# LKS_074DO_0319.net
KiCad netlist of a schematic drawn in Altium Designer
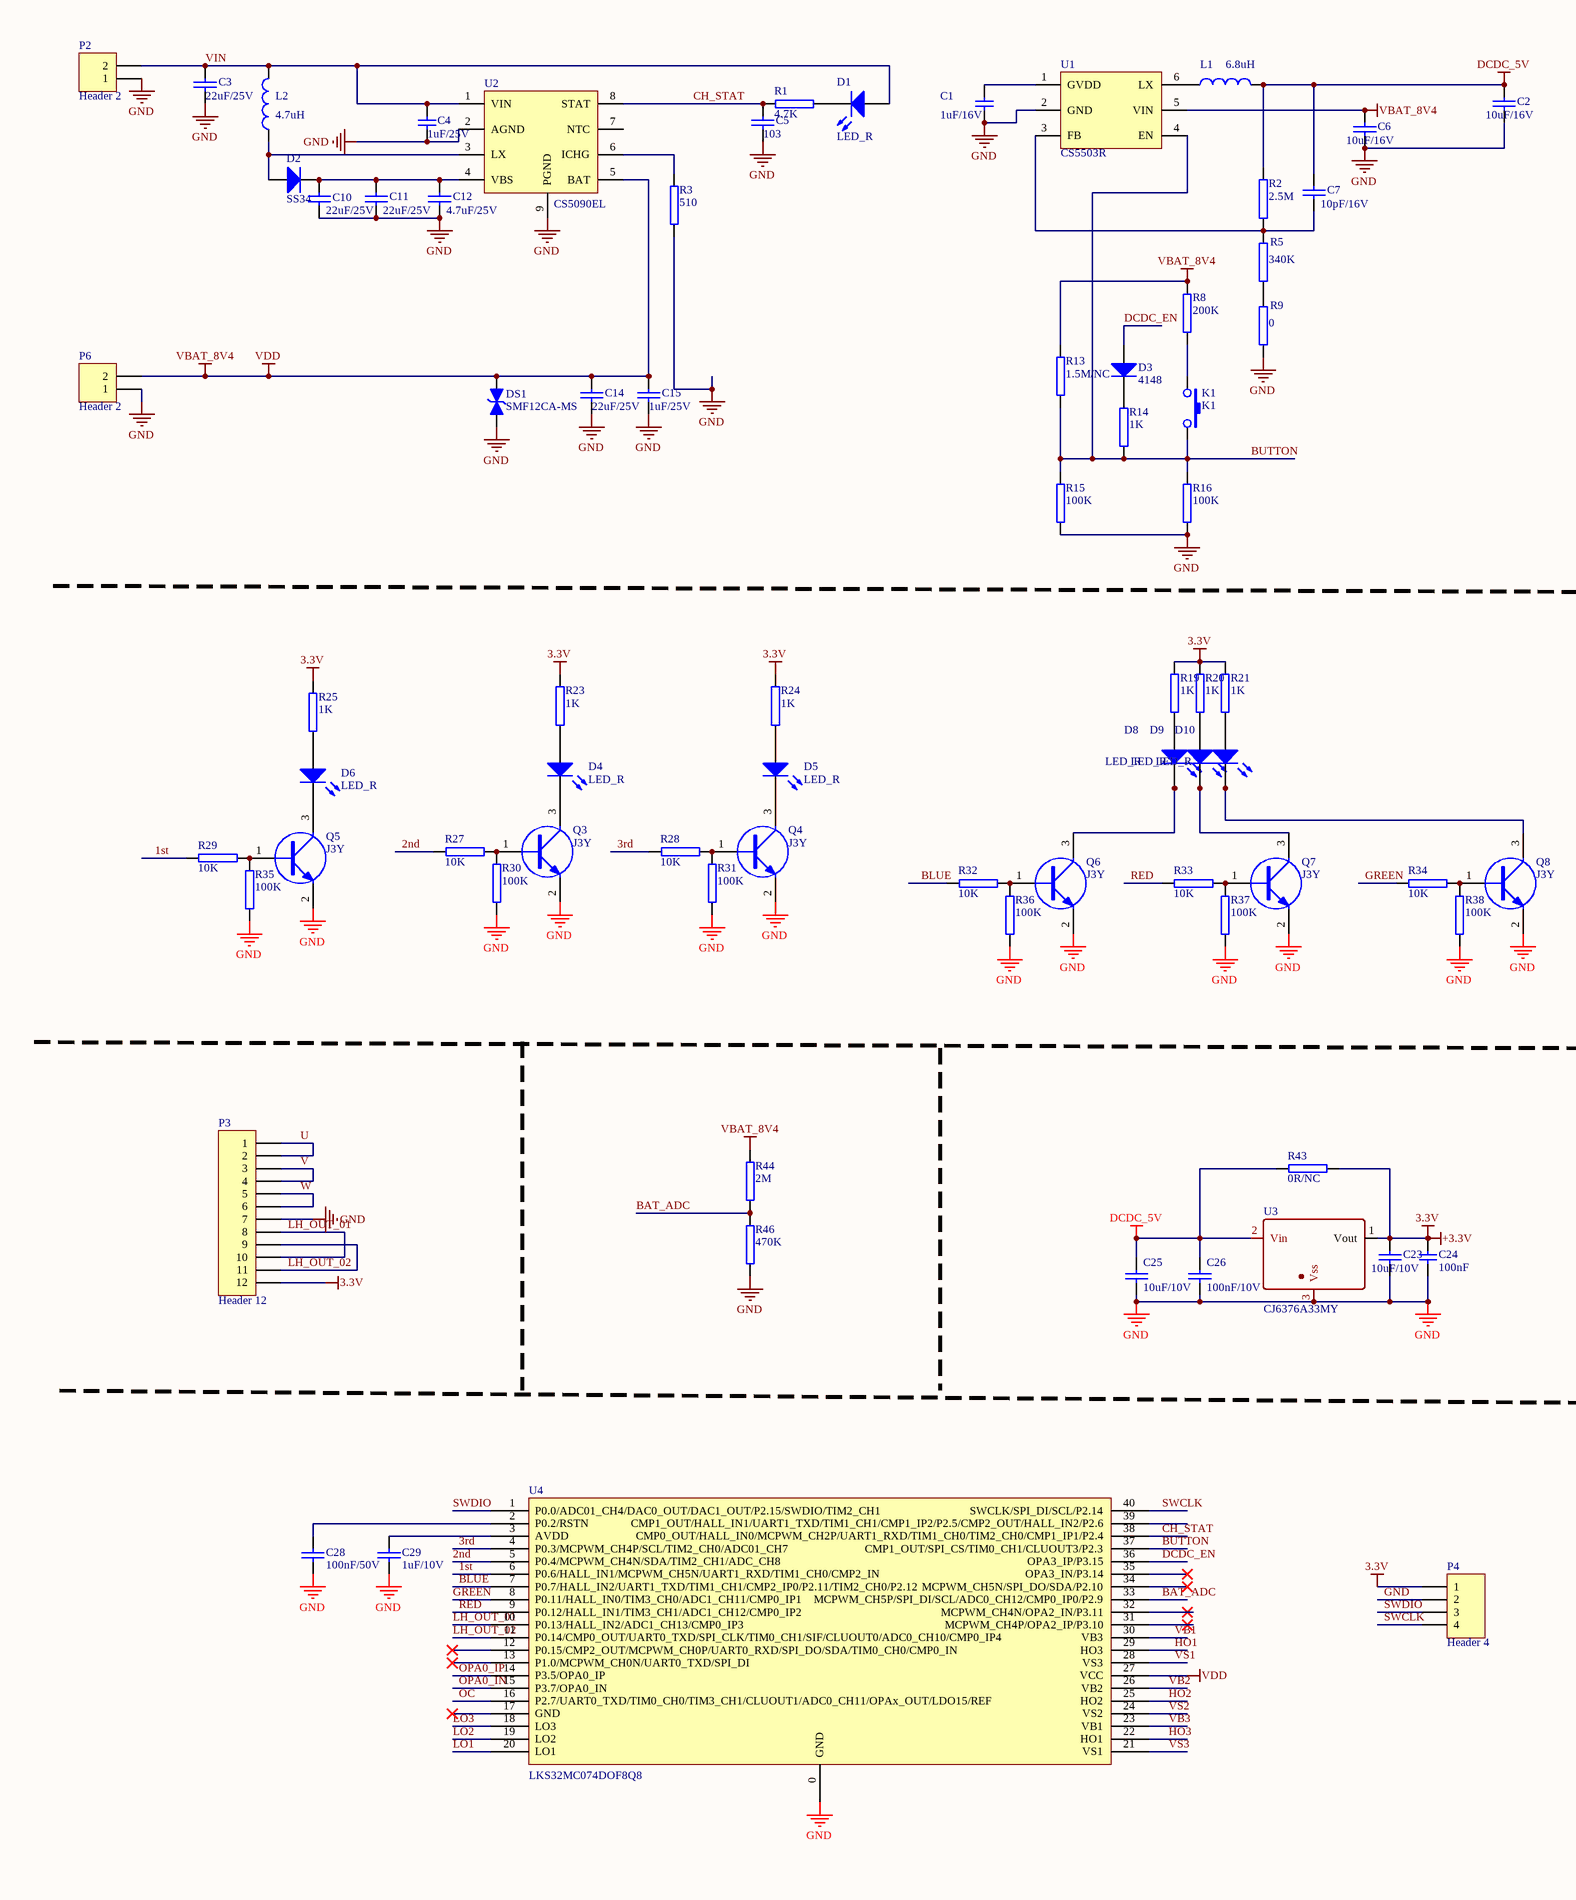
[diagram p0: LKS_074DO_0319.SchDoc, left]
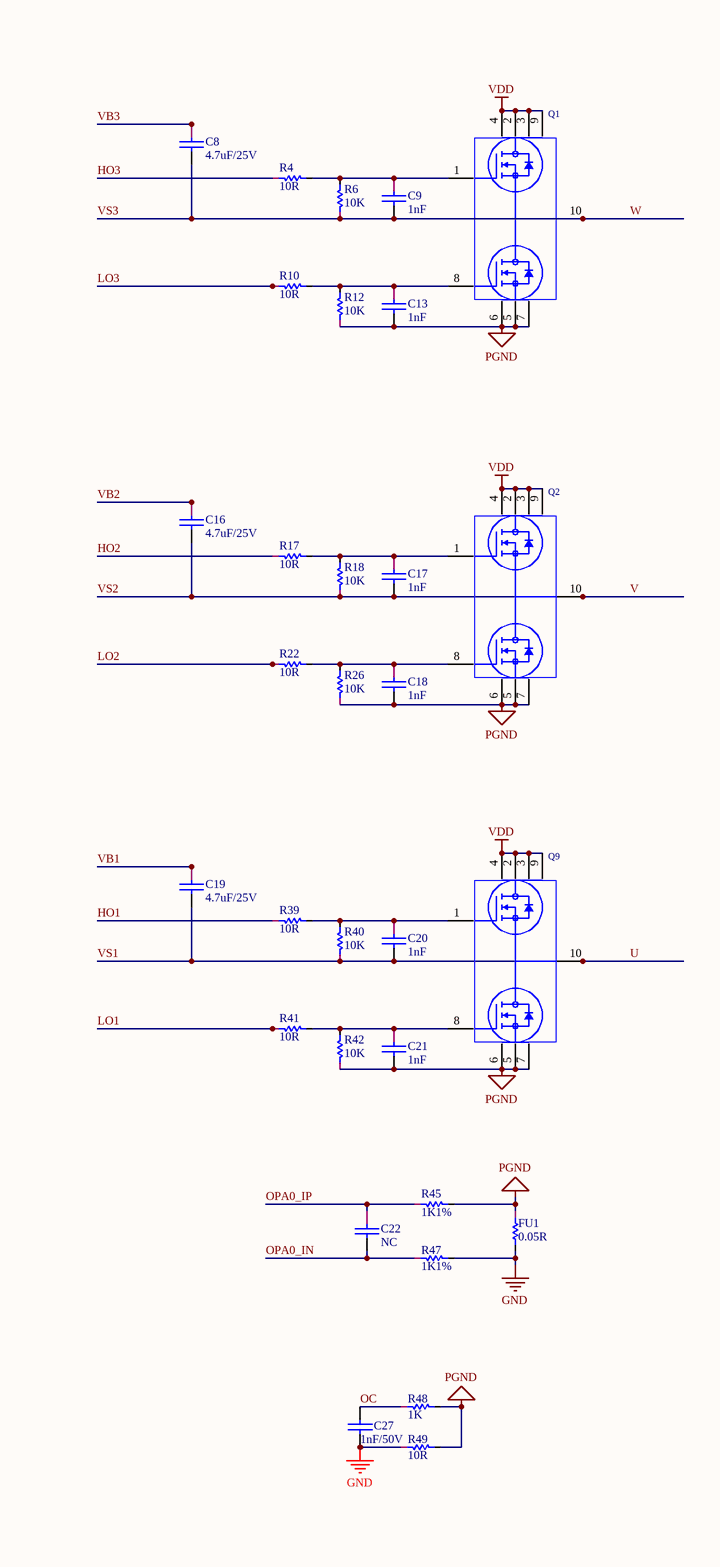
[diagram p1: LKS_074DO_0319.SchDoc, right]

(export (version "E")
  (design (tool "Eeschema 10.0.6"))
  (components
    (comp (ref "C1") (value "1uF/16V") (footprint "C 0402_M") (libsource (lib "") (part "CAP_2")))
    (comp (ref "C2")
      (value "10uF/16V")
      (footprint "C 0603_M")
      (description "Capacitor")
      (libsource (lib "") (part "CAP_1"))
    )
    (comp (ref "C3")
      (value "22uF/25V")
      (footprint "C 0603_M")
      (description "Capacitor")
      (libsource (lib "") (part "CAP_1"))
    )
    (comp (ref "C4") (value "1uF/25V") (footprint "C 0402_M") (libsource (lib "") (part "CAP_2")))
    (comp (ref "C5")
      (value "103")
      (footprint "R 0402_M")
      (description "Capacitor")
      (libsource (lib "") (part "CAP_1"))
    )
    (comp (ref "C6")
      (value "10uF/16V")
      (footprint "C 0603_M")
      (description "Capacitor")
      (libsource (lib "") (part "CAP_1"))
    )
    (comp (ref "C7")
      (value "10pF/16V")
      (footprint "C 0402_M")
      (description "Capacitor")
      (libsource (lib "") (part "CAP_1"))
    )
    (comp (ref "C8")
      (value "4.7uF/25V")
      (footprint "C 0402_M")
      (description "Capacitor")
      (libsource (lib "*") (part "CAP"))
    )
    (comp (ref "C9")
      (value "1nF")
      (footprint "C 0402_M")
      (description "Capacitor")
      (libsource (lib "*") (part "CAP"))
    )
    (comp (ref "C10")
      (value "22uF/25V")
      (footprint "C 0603_M")
      (description "Capacitor")
      (libsource (lib "") (part "CAP_1"))
    )
    (comp (ref "C11")
      (value "22uF/25V")
      (footprint "C 0603_M")
      (description "Capacitor")
      (libsource (lib "") (part "CAP_1"))
    )
    (comp (ref "C12")
      (value "4.7uF/25V")
      (footprint "C 0402_M")
      (description "Capacitor")
      (libsource (lib "") (part "CAP_1"))
    )
    (comp (ref "C13")
      (value "1nF")
      (footprint "C 0402_M")
      (description "Capacitor")
      (libsource (lib "*") (part "CAP"))
    )
    (comp (ref "C14")
      (value "22uF/25V")
      (footprint "C 0603_M")
      (description "Capacitor")
      (libsource (lib "") (part "CAP_1"))
    )
    (comp (ref "C15")
      (value "1uF/25V")
      (footprint "C 0402_M")
      (description "Capacitor")
      (libsource (lib "") (part "CAP_1"))
    )
    (comp (ref "C16")
      (value "4.7uF/25V")
      (footprint "C 0402_M")
      (description "Capacitor")
      (libsource (lib "*") (part "CAP"))
    )
    (comp (ref "C17")
      (value "1nF")
      (footprint "C 0402_M")
      (description "Capacitor")
      (libsource (lib "*") (part "CAP"))
    )
    (comp (ref "C18")
      (value "1nF")
      (footprint "C 0402_M")
      (description "Capacitor")
      (libsource (lib "*") (part "CAP"))
    )
    (comp (ref "C19")
      (value "4.7uF/25V")
      (footprint "C 0402_M")
      (description "Capacitor")
      (libsource (lib "*") (part "CAP"))
    )
    (comp (ref "C20")
      (value "1nF")
      (footprint "C 0402_M")
      (description "Capacitor")
      (libsource (lib "*") (part "CAP"))
    )
    (comp (ref "C21")
      (value "1nF")
      (footprint "C 0402_M")
      (description "Capacitor")
      (libsource (lib "*") (part "CAP"))
    )
    (comp (ref "C22")
      (value "NC")
      (footprint "C 0402_M")
      (description "Capacitor")
      (libsource (lib "*") (part "CAP"))
    )
    (comp (ref "C23")
      (value "10uF/10V")
      (footprint "C 0603_M")
      (description "Capacitor")
      (libsource (lib "") (part "CAP_1"))
    )
    (comp (ref "C24") (value "100nF") (footprint "C 0402_M") (libsource (lib "") (part "CAP_2")))
    (comp (ref "C25")
      (value "10uF/10V")
      (footprint "C 0603_M")
      (description "Capacitor")
      (libsource (lib "") (part "CAP_1"))
    )
    (comp (ref "C26")
      (value "100nF/10V")
      (footprint "C 0402_M")
      (description "Capacitor")
      (libsource (lib "") (part "CAP_1"))
    )
    (comp (ref "C27")
      (value "1nF/50V")
      (footprint "C 0402_M")
      (description "Capacitor")
      (libsource (lib "*") (part "C"))
    )
    (comp (ref "C28")
      (value "100nF/50V")
      (footprint "C 0402_M")
      (description "Capacitor")
      (libsource (lib "*") (part "C"))
    )
    (comp (ref "C29")
      (value "1uF/10V")
      (footprint "C 0402_M")
      (description "Capacitor")
      (libsource (lib "*") (part "C"))
    )
    (comp (ref "D1") (value "LED_R") (footprint "0603-LED") (libsource (lib "PuXun1") (part "LED")))
    (comp (ref "D2")
      (value "SS34")
      (footprint "SOD123FL")
      (description "Default Diode")
      (fields (field (name "PUBLISHER") "Altium Limited"))
      (libsource (lib "LKS034DO_Motor_0520_1") (part "Diode"))
    )
    (comp (ref "D3")
      (value "4148")
      (footprint "SOD-323")
      (description "Default Diode")
      (fields (field (name "PUBLISHER") "Altium Limited"))
      (libsource (lib "LKS034DO_Motor_0520_1") (part "Diode"))
    )
    (comp (ref "D4") (value "LED_R") (footprint "0603-LED") (libsource (lib "PuXun1") (part "LED")))
    (comp (ref "D5") (value "LED_R") (footprint "0603-LED") (libsource (lib "PuXun1") (part "LED")))
    (comp (ref "D6") (value "LED_R") (footprint "0603-LED") (libsource (lib "PuXun1") (part "LED")))
    (comp (ref "D8") (value "LED_R") (footprint "0603-LED") (libsource (lib "PuXun1") (part "LED")))
    (comp (ref "D9") (value "LED_R") (footprint "0603-LED") (libsource (lib "PuXun1") (part "LED")))
    (comp (ref "D10") (value "LED_R") (footprint "0603-LED") (libsource (lib "PuXun1") (part "LED")))
    (comp (ref "DS1")
      (value "SMF12CA-MS")
      (footprint "SOD-123F")
      (description "12V/19.9V")
      (libsource (lib "*") (part "DIODE-3"))
    )
    (comp (ref "FU1") (value "0.05R") (footprint "R 0805_M") (libsource (lib "*") (part "RAS")))
    (comp (ref "K1") (value "K1") (footprint "SMD3.3X3.3X2") (libsource (lib "SCHLIB_NEW") (part "K1")))
    (comp (ref "L1")
      (value "6.8uH")
      (footprint "SMD3.5X3 .2- duplicate")
      (description "Inductor")
      (fields (field (name "PUBLISHER") "Altium Limited"))
      (libsource (lib "Miscellaneous Devices") (part "Inductor"))
    )
    (comp (ref "L2")
      (value "4.7uH")
      (footprint "SMD3.5X3 .2- duplicate")
      (description "Inductor")
      (fields (field (name "PUBLISHER") "Altium Limited"))
      (libsource (lib "Miscellaneous Devices") (part "Inductor"))
    )
    (comp (ref "P2")
      (value "Header 2")
      (footprint "CONN_SMD_2P_0.6")
      (description "Header, 2-Pin")
      (fields (field (name "PUBLISHER") "Altium Limited"))
      (libsource (lib "Miscellaneous Connectors") (part "Header 2"))
    )
    (comp (ref "P3")
      (value "Header 12")
      (footprint "SMD-12")
      (description "Header, 12-Pin")
      (fields (field (name "PUBLISHER") "Altium Limited"))
      (libsource (lib "Miscellaneous Connectors") (part "Header 12"))
    )
    (comp (ref "P4")
      (value "Header 4")
      (footprint "HDR1X4")
      (description "Header, 4-Pin")
      (fields (field (name "PUBLISHER") "Altium Limited"))
      (libsource (lib "Miscellaneous Connectors") (part "Header 4"))
    )
    (comp (ref "P6")
      (value "Header 2")
      (footprint "CONN_SMD_2P_0.6")
      (description "Header, 2-Pin")
      (fields (field (name "PUBLISHER") "Altium Limited"))
      (libsource (lib "Miscellaneous Connectors") (part "Header 2"))
    )
    (comp (ref "Q1") (value "CJBM3020") (footprint "DFN-3X3_8") (libsource (lib "*") (part "CJBM3020")))
    (comp (ref "Q2") (value "CJBM3020") (footprint "DFN-3X3_8") (libsource (lib "*") (part "CJBM3020")))
    (comp (ref "Q3")
      (value "J3Y")
      (footprint "SOT-23")
      (description "NPN Transistor")
      (libsource (lib "*") (part "NPN"))
    )
    (comp (ref "Q4")
      (value "J3Y")
      (footprint "SOT-23")
      (description "NPN Transistor")
      (libsource (lib "*") (part "NPN"))
    )
    (comp (ref "Q5")
      (value "J3Y")
      (footprint "SOT-23")
      (description "NPN Transistor")
      (libsource (lib "*") (part "NPN"))
    )
    (comp (ref "Q6")
      (value "J3Y")
      (footprint "SOT-23")
      (description "NPN Transistor")
      (libsource (lib "*") (part "NPN"))
    )
    (comp (ref "Q7")
      (value "J3Y")
      (footprint "SOT-23")
      (description "NPN Transistor")
      (libsource (lib "*") (part "NPN"))
    )
    (comp (ref "Q8")
      (value "J3Y")
      (footprint "SOT-23")
      (description "NPN Transistor")
      (libsource (lib "*") (part "NPN"))
    )
    (comp (ref "Q9") (value "CJBM3020") (footprint "DFN-3X3_8") (libsource (lib "*") (part "CJBM3020")))
    (comp (ref "R1") (value "4.7K") (footprint "C 0402_M") (libsource (lib "*") (part "RES2_S")))
    (comp (ref "R2") (value "2.5M") (footprint "C 0402_M") (libsource (lib "*") (part "RES2_S")))
    (comp (ref "R3") (value "510") (footprint "R 0402_M") (libsource (lib "*") (part "RES2_S")))
    (comp (ref "R4") (value "10R") (footprint "R 0402_M") (libsource (lib "*") (part "RAS")))
    (comp (ref "R5") (value "340K") (footprint "C 0402_M") (libsource (lib "*") (part "RES2_S")))
    (comp (ref "R6") (value "10K") (footprint "R 0402_M") (libsource (lib "*") (part "RAS")))
    (comp (ref "R8") (value "200K") (footprint "C 0402_M") (libsource (lib "*") (part "RES2_S")))
    (comp (ref "R9") (value "0") (footprint "C 0402_M") (libsource (lib "*") (part "RES2_S")))
    (comp (ref "R10") (value "10R") (footprint "R 0402_M") (libsource (lib "*") (part "RAS")))
    (comp (ref "R12") (value "10K") (footprint "R 0402_M") (libsource (lib "*") (part "RAS")))
    (comp (ref "R13") (value "1.5M/NC") (footprint "C 0402_M") (libsource (lib "*") (part "RES2_S")))
    (comp (ref "R14") (value "1K") (footprint "C 0402_M") (libsource (lib "*") (part "RES2_S")))
    (comp (ref "R15") (value "100K") (footprint "C 0402_M") (libsource (lib "*") (part "RES2_S")))
    (comp (ref "R16") (value "100K") (footprint "C 0402_M") (libsource (lib "*") (part "RES2_S")))
    (comp (ref "R17") (value "10R") (footprint "R 0402_M") (libsource (lib "*") (part "RAS")))
    (comp (ref "R18") (value "10K") (footprint "R 0402_M") (libsource (lib "*") (part "RAS")))
    (comp (ref "R19") (value "1K") (footprint "C 0402_M") (libsource (lib "*") (part "RES2_S")))
    (comp (ref "R20") (value "1K") (footprint "C 0402_M") (libsource (lib "*") (part "RES2_S")))
    (comp (ref "R21") (value "1K") (footprint "C 0402_M") (libsource (lib "*") (part "RES2_S")))
    (comp (ref "R22") (value "10R") (footprint "R 0402_M") (libsource (lib "*") (part "RAS")))
    (comp (ref "R23") (value "1K") (footprint "C 0402_M") (libsource (lib "*") (part "RES2_S")))
    (comp (ref "R24") (value "1K") (footprint "C 0402_M") (libsource (lib "*") (part "RES2_S")))
    (comp (ref "R25") (value "1K") (footprint "C 0402_M") (libsource (lib "*") (part "RES2_S")))
    (comp (ref "R26") (value "10K") (footprint "R 0402_M") (libsource (lib "*") (part "RAS")))
    (comp (ref "R27") (value "10K") (footprint "C 0402_M") (libsource (lib "*") (part "RES2_S")))
    (comp (ref "R28") (value "10K") (footprint "C 0402_M") (libsource (lib "*") (part "RES2_S")))
    (comp (ref "R29") (value "10K") (footprint "C 0402_M") (libsource (lib "*") (part "RES2_S")))
    (comp (ref "R30") (value "100K") (footprint "C 0402_M") (libsource (lib "*") (part "RES2_S")))
    (comp (ref "R31") (value "100K") (footprint "C 0402_M") (libsource (lib "*") (part "RES2_S")))
    (comp (ref "R32") (value "10K") (footprint "C 0402_M") (libsource (lib "*") (part "RES2_S")))
    (comp (ref "R33") (value "10K") (footprint "C 0402_M") (libsource (lib "*") (part "RES2_S")))
    (comp (ref "R34") (value "10K") (footprint "C 0402_M") (libsource (lib "*") (part "RES2_S")))
    (comp (ref "R35") (value "100K") (footprint "C 0402_M") (libsource (lib "*") (part "RES2_S")))
    (comp (ref "R36") (value "100K") (footprint "C 0402_M") (libsource (lib "*") (part "RES2_S")))
    (comp (ref "R37") (value "100K") (footprint "C 0402_M") (libsource (lib "*") (part "RES2_S")))
    (comp (ref "R38") (value "100K") (footprint "C 0402_M") (libsource (lib "*") (part "RES2_S")))
    (comp (ref "R39") (value "10R") (footprint "R 0402_M") (libsource (lib "*") (part "RAS")))
    (comp (ref "R40") (value "10K") (footprint "R 0402_M") (libsource (lib "*") (part "RAS")))
    (comp (ref "R41") (value "10R") (footprint "R 0402_M") (libsource (lib "*") (part "RAS")))
    (comp (ref "R42") (value "10K") (footprint "R 0402_M") (libsource (lib "*") (part "RAS")))
    (comp (ref "R43") (value "0R/NC") (footprint "0603") (libsource (lib "*") (part "RES2_S")))
    (comp (ref "R44") (value "2M") (footprint "C 0402_M") (libsource (lib "*") (part "RES2_S")))
    (comp (ref "R45") (value "1K1%") (footprint "R 0402_M") (libsource (lib "*") (part "RAS")))
    (comp (ref "R46") (value "470K") (footprint "C 0402_M") (libsource (lib "*") (part "RES2_S")))
    (comp (ref "R47") (value "1K1%") (footprint "R 0402_M") (libsource (lib "*") (part "RAS")))
    (comp (ref "R48") (value "1K") (footprint "R 0402_M") (libsource (lib "*") (part "RAS")))
    (comp (ref "R49") (value "10R") (footprint "R 0402_M") (libsource (lib "*") (part "RAS")))
    (comp (ref "U1")
      (value "CS5503R")
      (footprint "SOT23-6L")
      (libsource (lib "LKS034DO_Motor_0520_1") (part "CS5503R"))
    )
    (comp (ref "U2")
      (value "CS5090EL")
      (footprint "DFN2X2_8_0.5")
      (libsource (lib "LKS034DO_Motor_0520_1") (part "CS5090EL"))
    )
    (comp (ref "U3")
      (value "CJ6376A33MY")
      (footprint "SOT-23")
      (libsource (lib "LKS034DO_Motor_0520_1") (part "78L15"))
    )
    (comp (ref "U4")
      (value "LKS32MC074DOF8Q8")
      (footprint "QFN40")
      (description "芯片")
      (libsource (lib "Q_LINKO_V1.0") (part "LKS32MC074DF8Q8"))
    )
  )
  (nets
    (net (code "1") (name "+3.3V") (class "Default")
      (node (ref "C23") (pin "2") (pinfunction "2_2") (pintype "passive"))
      (node (ref "C24") (pin "1") (pinfunction "1_1") (pintype "passive"))
      (node (ref "P3") (pin "12") (pinfunction "12_12") (pintype "passive"))
      (node (ref "P4") (pin "1") (pinfunction "1_1") (pintype "passive"))
      (node (ref "R19") (pin "2") (pinfunction "2_2") (pintype "passive"))
      (node (ref "R20") (pin "2") (pinfunction "2_2") (pintype "passive"))
      (node (ref "R21") (pin "2") (pinfunction "2_2") (pintype "passive"))
      (node (ref "R23") (pin "2") (pinfunction "2_2") (pintype "passive"))
      (node (ref "R24") (pin "2") (pinfunction "2_2") (pintype "passive"))
      (node (ref "R25") (pin "2") (pinfunction "2_2") (pintype "passive"))
      (node (ref "R43") (pin "2") (pinfunction "2_2") (pintype "passive"))
      (node (ref "U3") (pin "1") (pinfunction "Vout_1") (pintype "passive"))
    )
    (net (code "2") (name "/1st") (class "Default")
      (node (ref "R29") (pin "2") (pinfunction "2_2") (pintype "passive"))
      (node (ref "U4") (pin "6") (pinfunction "P0.6/HALL_IN1/MCPWM_CH5N/UART1_RXD/TIM1_CH0/CMP2_IN_6") (pintype "passive"))
    )
    (net (code "3") (name "/2nd") (class "Default")
      (node (ref "R27") (pin "2") (pinfunction "2_2") (pintype "passive"))
      (node (ref "U4") (pin "5") (pinfunction "P0.4/MCPWM_CH4N/SDA/TIM2_CH1/ADC_CH8_5") (pintype "passive"))
    )
    (net (code "4") (name "/3rd") (class "Default")
      (node (ref "R28") (pin "2") (pinfunction "2_2") (pintype "passive"))
      (node (ref "U4") (pin "4") (pinfunction "P0.3/MCPWM_CH4P/SCL/TIM2_CH0/ADC01_CH7_4") (pintype "passive"))
    )
    (net (code "5") (name "/BAT_ADC") (class "Default")
      (node (ref "R44") (pin "2") (pinfunction "2_2") (pintype "passive"))
      (node (ref "R46") (pin "1") (pinfunction "1_1") (pintype "passive"))
      (node (ref "U4") (pin "33") (pinfunction "MCPWM_CH5P/SPI_DI/SCL/ADC0_CH12/CMP0_IP0/P2.9_33") (pintype "passive"))
    )
    (net (code "6") (name "/BLUE") (class "Default")
      (node (ref "R32") (pin "2") (pinfunction "2_2") (pintype "passive"))
      (node (ref "U4") (pin "7") (pinfunction "P0.7/HALL_IN2/UART1_TXD/TIM1_CH1/CMP2_IP0/P2.11/TIM2_CH0/P2.12_7") (pintype "passive"))
    )
    (net (code "7") (name "/BUTTON") (class "Default")
      (node (ref "K1") (pin "2") (pintype "passive"))
      (node (ref "R13") (pin "2") (pinfunction "2_2") (pintype "passive"))
      (node (ref "R14") (pin "2") (pinfunction "2_2") (pintype "passive"))
      (node (ref "R15") (pin "2") (pinfunction "2_2") (pintype "passive"))
      (node (ref "R16") (pin "1") (pinfunction "1_1") (pintype "passive"))
      (node (ref "U1") (pin "4") (pinfunction "EN_4") (pintype "passive"))
      (node (ref "U4") (pin "37") (pinfunction "CMP1_OUT/SPI_CS/TIM0_CH1/CLUOUT3/P2.3_37") (pintype "passive"))
    )
    (net (code "8") (name "/CH_STAT") (class "Default")
      (node (ref "C5") (pin "2") (pinfunction "2_2") (pintype "passive"))
      (node (ref "R1") (pin "1") (pinfunction "1_1") (pintype "passive"))
      (node (ref "U2") (pin "8") (pinfunction "STAT_8") (pintype "passive"))
      (node (ref "U4") (pin "38") (pinfunction "CMP0_OUT/HALL_IN0/MCPWM_CH2P/UART1_RXD/TIM1_CH0/TIM2_CH0/CMP1_IP1/P2.4_38") (pintype "passive"))
    )
    (net (code "9") (name "/DCDC_EN") (class "Default")
      (node (ref "D3") (pin "1") (pinfunction "A_1") (pintype "passive"))
      (node (ref "U4") (pin "36") (pinfunction "OPA3_IP/P3.15_36") (pintype "passive"))
    )
    (net (code "10") (name "/GREEN") (class "Default")
      (node (ref "R34") (pin "2") (pinfunction "2_2") (pintype "passive"))
      (node (ref "U4") (pin "8") (pinfunction "P0.11/HALL_IN0/TIM3_CH0/ADC1_CH11/CMP0_IP1_8") (pintype "passive"))
    )
    (net (code "11") (name "/HO1") (class "Default")
      (node (ref "R39") (pin "2") (pinfunction "2_2") (pintype "passive"))
      (node (ref "U4") (pin "29") (pinfunction "HO3_29") (pintype "passive"))
    )
    (net (code "12") (name "/HO2") (class "Default")
      (node (ref "R17") (pin "2") (pinfunction "2_2") (pintype "passive"))
      (node (ref "U4") (pin "25") (pinfunction "HO2_25") (pintype "passive"))
    )
    (net (code "13") (name "/HO3") (class "Default")
      (node (ref "R4") (pin "2") (pinfunction "2_2") (pintype "passive"))
      (node (ref "U4") (pin "22") (pinfunction "HO1_22") (pintype "passive"))
    )
    (net (code "14") (name "/LH_OUT_01") (class "Default")
      (node (ref "P3") (pin "10") (pinfunction "10_10") (pintype "passive"))
      (node (ref "P3") (pin "8") (pinfunction "8_8") (pintype "passive"))
      (node (ref "U4") (pin "10") (pinfunction "P0.13/HALL_IN2/ADC1_CH13/CMP0_IP3_10") (pintype "passive"))
    )
    (net (code "15") (name "/LH_OUT_02") (class "Default")
      (node (ref "P3") (pin "11") (pinfunction "11_11") (pintype "passive"))
      (node (ref "P3") (pin "9") (pinfunction "9_9") (pintype "passive"))
      (node (ref "U4") (pin "11") (pinfunction "P0.14/CMP0_OUT/UART0_TXD/SPI_CLK/TIM0_CH1/SIF/CLUOUT0/ADC0_CH10/CMP0_IP4_11") (pintype "passive"))
    )
    (net (code "16") (name "/LO1") (class "Default")
      (node (ref "R41") (pin "2") (pinfunction "2_2") (pintype "passive"))
      (node (ref "U4") (pin "20") (pinfunction "LO1_20") (pintype "passive"))
    )
    (net (code "17") (name "/LO2") (class "Default")
      (node (ref "R22") (pin "2") (pinfunction "2_2") (pintype "passive"))
      (node (ref "U4") (pin "19") (pinfunction "LO2_19") (pintype "passive"))
    )
    (net (code "18") (name "/LO3") (class "Default")
      (node (ref "R10") (pin "2") (pinfunction "2_2") (pintype "passive"))
      (node (ref "U4") (pin "18") (pinfunction "LO3_18") (pintype "passive"))
    )
    (net (code "19") (name "/OC") (class "Default")
      (node (ref "C27") (pin "2") (pinfunction "2_2") (pintype "passive"))
      (node (ref "R48") (pin "2") (pinfunction "2_2") (pintype "passive"))
      (node (ref "U4") (pin "16") (pinfunction "P2.7/UART0_TXD/TIM0_CH0/TIM3_CH1/CLUOUT1/ADC0_CH11/OPAx_OUT/LDO15/REF_16") (pintype "passive"))
    )
    (net (code "20") (name "/OPA0_IN") (class "Default")
      (node (ref "C22") (pin "1") (pinfunction "1_1") (pintype "passive"))
      (node (ref "R47") (pin "2") (pinfunction "2_2") (pintype "passive"))
      (node (ref "U4") (pin "15") (pinfunction "P3.7/OPA0_IN_15") (pintype "passive"))
    )
    (net (code "21") (name "/OPA0_IP") (class "Default")
      (node (ref "C22") (pin "2") (pinfunction "2_2") (pintype "passive"))
      (node (ref "R45") (pin "2") (pinfunction "2_2") (pintype "passive"))
      (node (ref "U4") (pin "14") (pinfunction "P3.5/OPA0_IP_14") (pintype "passive"))
    )
    (net (code "22") (name "/RED") (class "Default")
      (node (ref "R33") (pin "2") (pinfunction "2_2") (pintype "passive"))
      (node (ref "U4") (pin "9") (pinfunction "P0.12/HALL_IN1/TIM3_CH1/ADC1_CH12/CMP0_IP2_9") (pintype "passive"))
    )
    (net (code "23") (name "/SWCLK") (class "Default")
      (node (ref "P4") (pin "4") (pinfunction "4_4") (pintype "passive"))
      (node (ref "U4") (pin "40") (pinfunction "SWCLK/SPI_DI/SCL/P2.14_40") (pintype "passive"))
    )
    (net (code "24") (name "/SWDIO") (class "Default")
      (node (ref "P4") (pin "3") (pinfunction "3_3") (pintype "passive"))
      (node (ref "U4") (pin "1") (pinfunction "P0.0/ADC01_CH4/DAC0_OUT/DAC1_OUT/P2.15/SWDIO/TIM2_CH1_1") (pintype "passive"))
    )
    (net (code "25") (name "/U") (class "Default")
      (node (ref "C19") (pin "1") (pinfunction "1_1") (pintype "passive"))
      (node (ref "C20") (pin "1") (pinfunction "1_1") (pintype "passive"))
      (node (ref "P3") (pin "1") (pinfunction "1_1") (pintype "passive"))
      (node (ref "P3") (pin "2") (pinfunction "2_2") (pintype "passive"))
      (node (ref "Q9") (pin "10") (pinfunction "S1/D2_10") (pintype "passive"))
      (node (ref "R40") (pin "2") (pinfunction "2_2") (pintype "passive"))
      (node (ref "U4") (pin "28") (pinfunction "VS3_28") (pintype "passive"))
    )
    (net (code "26") (name "/V") (class "Default")
      (node (ref "C16") (pin "1") (pinfunction "1_1") (pintype "passive"))
      (node (ref "C17") (pin "1") (pinfunction "1_1") (pintype "passive"))
      (node (ref "P3") (pin "3") (pinfunction "3_3") (pintype "passive"))
      (node (ref "P3") (pin "4") (pinfunction "4_4") (pintype "passive"))
      (node (ref "Q2") (pin "10") (pinfunction "S1/D2_10") (pintype "passive"))
      (node (ref "R18") (pin "2") (pinfunction "2_2") (pintype "passive"))
      (node (ref "U4") (pin "24") (pinfunction "VS2_24") (pintype "passive"))
    )
    (net (code "27") (name "/VB1") (class "Default")
      (node (ref "C19") (pin "2") (pinfunction "2_2") (pintype "passive"))
      (node (ref "U4") (pin "30") (pinfunction "VB3_30") (pintype "passive"))
    )
    (net (code "28") (name "/VB2") (class "Default")
      (node (ref "C16") (pin "2") (pinfunction "2_2") (pintype "passive"))
      (node (ref "U4") (pin "26") (pinfunction "VB2_26") (pintype "passive"))
    )
    (net (code "29") (name "/VB3") (class "Default")
      (node (ref "C8") (pin "2") (pinfunction "2_2") (pintype "passive"))
      (node (ref "U4") (pin "23") (pinfunction "VB1_23") (pintype "passive"))
    )
    (net (code "30") (name "/VIN") (class "Default")
      (node (ref "C3") (pin "2") (pinfunction "2_2") (pintype "passive"))
      (node (ref "C4") (pin "1") (pinfunction "1_1") (pintype "passive"))
      (node (ref "D1") (pin "1") (pinfunction "A_1") (pintype "passive"))
      (node (ref "L2") (pin "2") (pinfunction "2_2") (pintype "passive"))
      (node (ref "P2") (pin "2") (pinfunction "2_2") (pintype "passive"))
      (node (ref "U2") (pin "1") (pinfunction "VIN_1") (pintype "passive"))
    )
    (net (code "31") (name "/VS3") (class "Default")
      (node (ref "C8") (pin "1") (pinfunction "1_1") (pintype "passive"))
      (node (ref "C9") (pin "1") (pinfunction "1_1") (pintype "passive"))
      (node (ref "P3") (pin "5") (pinfunction "5_5") (pintype "passive"))
      (node (ref "P3") (pin "6") (pinfunction "6_6") (pintype "passive"))
      (node (ref "Q1") (pin "10") (pinfunction "S1/D2_10") (pintype "passive"))
      (node (ref "R6") (pin "2") (pinfunction "2_2") (pintype "passive"))
      (node (ref "U4") (pin "21") (pinfunction "VS1_21") (pintype "passive"))
    )
    (net (code "32") (name "DCDC_5V") (class "Default")
      (node (ref "C2") (pin "2") (pinfunction "2_2") (pintype "passive"))
      (node (ref "C25") (pin "2") (pinfunction "2_2") (pintype "passive"))
      (node (ref "C26") (pin "1") (pinfunction "1_1") (pintype "passive"))
      (node (ref "C7") (pin "2") (pinfunction "2_2") (pintype "passive"))
      (node (ref "L1") (pin "2") (pinfunction "2_2") (pintype "passive"))
      (node (ref "R2") (pin "1") (pinfunction "1_1") (pintype "passive"))
      (node (ref "R43") (pin "1") (pinfunction "1_1") (pintype "passive"))
      (node (ref "U3") (pin "2") (pinfunction "Vin_2") (pintype "passive"))
    )
    (net (code "33") (name "GND") (class "Default")
      (node (ref "C1") (pin "1") (pinfunction "1_1") (pintype "passive"))
      (node (ref "C10") (pin "1") (pinfunction "1_1") (pintype "passive"))
      (node (ref "C11") (pin "1") (pinfunction "1_1") (pintype "passive"))
      (node (ref "C12") (pin "1") (pinfunction "1_1") (pintype "passive"))
      (node (ref "C14") (pin "1") (pinfunction "1_1") (pintype "passive"))
      (node (ref "C15") (pin "1") (pinfunction "1_1") (pintype "passive"))
      (node (ref "C2") (pin "1") (pinfunction "1_1") (pintype "passive"))
      (node (ref "C23") (pin "1") (pinfunction "1_1") (pintype "passive"))
      (node (ref "C24") (pin "2") (pinfunction "2_2") (pintype "passive"))
      (node (ref "C25") (pin "1") (pinfunction "1_1") (pintype "passive"))
      (node (ref "C26") (pin "2") (pinfunction "2_2") (pintype "passive"))
      (node (ref "C27") (pin "1") (pinfunction "1_1") (pintype "passive"))
      (node (ref "C28") (pin "2") (pinfunction "2_2") (pintype "passive"))
      (node (ref "C29") (pin "1") (pinfunction "1_1") (pintype "passive"))
      (node (ref "C3") (pin "1") (pinfunction "1_1") (pintype "passive"))
      (node (ref "C4") (pin "2") (pinfunction "2_2") (pintype "passive"))
      (node (ref "C5") (pin "1") (pinfunction "1_1") (pintype "passive"))
      (node (ref "C6") (pin "1") (pinfunction "1_1") (pintype "passive"))
      (node (ref "DS1") (pin "2") (pinfunction "K_2") (pintype "passive"))
      (node (ref "FU1") (pin "1") (pinfunction "1_1") (pintype "passive"))
      (node (ref "P2") (pin "1") (pinfunction "1_1") (pintype "passive"))
      (node (ref "P3") (pin "7") (pinfunction "7_7") (pintype "passive"))
      (node (ref "P4") (pin "2") (pinfunction "2_2") (pintype "passive"))
      (node (ref "P6") (pin "1") (pinfunction "1_1") (pintype "passive"))
      (node (ref "Q3") (pin "2") (pinfunction "E_2") (pintype "passive"))
      (node (ref "Q4") (pin "2") (pinfunction "E_2") (pintype "passive"))
      (node (ref "Q5") (pin "2") (pinfunction "E_2") (pintype "passive"))
      (node (ref "Q6") (pin "2") (pinfunction "E_2") (pintype "passive"))
      (node (ref "Q7") (pin "2") (pinfunction "E_2") (pintype "passive"))
      (node (ref "Q8") (pin "2") (pinfunction "E_2") (pintype "passive"))
      (node (ref "R15") (pin "1") (pinfunction "1_1") (pintype "passive"))
      (node (ref "R16") (pin "2") (pinfunction "2_2") (pintype "passive"))
      (node (ref "R3") (pin "2") (pinfunction "2_2") (pintype "passive"))
      (node (ref "R30") (pin "2") (pinfunction "2_2") (pintype "passive"))
      (node (ref "R31") (pin "2") (pinfunction "2_2") (pintype "passive"))
      (node (ref "R35") (pin "2") (pinfunction "2_2") (pintype "passive"))
      (node (ref "R36") (pin "2") (pinfunction "2_2") (pintype "passive"))
      (node (ref "R37") (pin "2") (pinfunction "2_2") (pintype "passive"))
      (node (ref "R38") (pin "2") (pinfunction "2_2") (pintype "passive"))
      (node (ref "R46") (pin "2") (pinfunction "2_2") (pintype "passive"))
      (node (ref "R47") (pin "1") (pinfunction "1_1") (pintype "passive"))
      (node (ref "R49") (pin "2") (pinfunction "2_2") (pintype "passive"))
      (node (ref "R9") (pin "2") (pinfunction "2_2") (pintype "passive"))
      (node (ref "U1") (pin "2") (pinfunction "GND_2") (pintype "passive"))
      (node (ref "U2") (pin "2") (pinfunction "AGND_2") (pintype "passive"))
      (node (ref "U2") (pin "9") (pinfunction "PGND_9") (pintype "passive"))
      (node (ref "U3") (pin "3") (pinfunction "Vss_3") (pintype "passive"))
      (node (ref "U4") (pin "0") (pinfunction "GND_0") (pintype "passive"))
    )
    (net (code "34") (name "Net-(D1-K)") (class "Default")
      (node (ref "D1") (pin "2") (pinfunction "K_2") (pintype "passive"))
      (node (ref "R1") (pin "2") (pinfunction "2_2") (pintype "passive"))
    )
    (net (code "35") (name "Net-(D2-A)") (class "Default")
      (node (ref "D2") (pin "1") (pinfunction "A_1") (pintype "passive"))
      (node (ref "L2") (pin "1") (pinfunction "1_1") (pintype "passive"))
      (node (ref "U2") (pin "3") (pinfunction "LX_3") (pintype "passive"))
    )
    (net (code "36") (name "Net-(D2-K)") (class "Default")
      (node (ref "C10") (pin "2") (pinfunction "2_2") (pintype "passive"))
      (node (ref "C11") (pin "2") (pinfunction "2_2") (pintype "passive"))
      (node (ref "C12") (pin "2") (pinfunction "2_2") (pintype "passive"))
      (node (ref "D2") (pin "2") (pinfunction "K_2") (pintype "passive"))
      (node (ref "U2") (pin "4") (pinfunction "VBS_4") (pintype "passive"))
    )
    (net (code "37") (name "Net-(D3-K)") (class "Default")
      (node (ref "D3") (pin "2") (pinfunction "K_2") (pintype "passive"))
      (node (ref "R14") (pin "1") (pinfunction "1_1") (pintype "passive"))
    )
    (net (code "38") (name "Net-(D4-A)") (class "Default")
      (node (ref "D4") (pin "1") (pinfunction "A_1") (pintype "passive"))
      (node (ref "R23") (pin "1") (pinfunction "1_1") (pintype "passive"))
    )
    (net (code "39") (name "Net-(D4-K)") (class "Default")
      (node (ref "D4") (pin "2") (pinfunction "K_2") (pintype "passive"))
      (node (ref "Q3") (pin "3") (pinfunction "C_3") (pintype "passive"))
    )
    (net (code "40") (name "Net-(D5-A)") (class "Default")
      (node (ref "D5") (pin "1") (pinfunction "A_1") (pintype "passive"))
      (node (ref "R24") (pin "1") (pinfunction "1_1") (pintype "passive"))
    )
    (net (code "41") (name "Net-(D5-K)") (class "Default")
      (node (ref "D5") (pin "2") (pinfunction "K_2") (pintype "passive"))
      (node (ref "Q4") (pin "3") (pinfunction "C_3") (pintype "passive"))
    )
    (net (code "42") (name "Net-(D6-A)") (class "Default")
      (node (ref "D6") (pin "1") (pinfunction "A_1") (pintype "passive"))
      (node (ref "R25") (pin "1") (pinfunction "1_1") (pintype "passive"))
    )
    (net (code "43") (name "Net-(D6-K)") (class "Default")
      (node (ref "D6") (pin "2") (pinfunction "K_2") (pintype "passive"))
      (node (ref "Q5") (pin "3") (pinfunction "C_3") (pintype "passive"))
    )
    (net (code "44") (name "Net-(D8-A)") (class "Default")
      (node (ref "D8") (pin "1") (pinfunction "A_1") (pintype "passive"))
      (node (ref "R19") (pin "1") (pinfunction "1_1") (pintype "passive"))
    )
    (net (code "45") (name "Net-(D8-K)") (class "Default")
      (node (ref "D8") (pin "2") (pinfunction "K_2") (pintype "passive"))
      (node (ref "Q6") (pin "3") (pinfunction "C_3") (pintype "passive"))
    )
    (net (code "46") (name "Net-(D9-A)") (class "Default")
      (node (ref "D9") (pin "1") (pinfunction "A_1") (pintype "passive"))
      (node (ref "R20") (pin "1") (pinfunction "1_1") (pintype "passive"))
    )
    (net (code "47") (name "Net-(D9-K)") (class "Default")
      (node (ref "D9") (pin "2") (pinfunction "K_2") (pintype "passive"))
      (node (ref "Q7") (pin "3") (pinfunction "C_3") (pintype "passive"))
    )
    (net (code "48") (name "Net-(D10-A)") (class "Default")
      (node (ref "D10") (pin "1") (pinfunction "A_1") (pintype "passive"))
      (node (ref "R21") (pin "1") (pinfunction "1_1") (pintype "passive"))
    )
    (net (code "49") (name "Net-(D10-K)") (class "Default")
      (node (ref "D10") (pin "2") (pinfunction "K_2") (pintype "passive"))
      (node (ref "Q8") (pin "3") (pinfunction "C_3") (pintype "passive"))
    )
    (net (code "50") (name "Net-(K1-Pad1)") (class "Default")
      (node (ref "K1") (pin "1") (pintype "passive"))
      (node (ref "R8") (pin "1") (pinfunction "1_1") (pintype "passive"))
    )
    (net (code "51") (name "Net-(Q1-G1)") (class "Default")
      (node (ref "C9") (pin "2") (pinfunction "2_2") (pintype "passive"))
      (node (ref "Q1") (pin "1") (pinfunction "G1_1") (pintype "passive"))
      (node (ref "R4") (pin "1") (pinfunction "1_1") (pintype "passive"))
      (node (ref "R6") (pin "1") (pinfunction "1_1") (pintype "passive"))
    )
    (net (code "52") (name "Net-(Q1-G2)") (class "Default")
      (node (ref "C13") (pin "2") (pinfunction "2_2") (pintype "passive"))
      (node (ref "Q1") (pin "8") (pinfunction "G2_8") (pintype "passive"))
      (node (ref "R10") (pin "1") (pinfunction "1_1") (pintype "passive"))
      (node (ref "R12") (pin "1") (pinfunction "1_1") (pintype "passive"))
    )
    (net (code "53") (name "Net-(Q2-G1)") (class "Default")
      (node (ref "C17") (pin "2") (pinfunction "2_2") (pintype "passive"))
      (node (ref "Q2") (pin "1") (pinfunction "G1_1") (pintype "passive"))
      (node (ref "R17") (pin "1") (pinfunction "1_1") (pintype "passive"))
      (node (ref "R18") (pin "1") (pinfunction "1_1") (pintype "passive"))
    )
    (net (code "54") (name "Net-(Q2-G2)") (class "Default")
      (node (ref "C18") (pin "2") (pinfunction "2_2") (pintype "passive"))
      (node (ref "Q2") (pin "8") (pinfunction "G2_8") (pintype "passive"))
      (node (ref "R22") (pin "1") (pinfunction "1_1") (pintype "passive"))
      (node (ref "R26") (pin "1") (pinfunction "1_1") (pintype "passive"))
    )
    (net (code "55") (name "Net-(Q3-B)") (class "Default")
      (node (ref "Q3") (pin "1") (pinfunction "B_1") (pintype "passive"))
      (node (ref "R27") (pin "1") (pinfunction "1_1") (pintype "passive"))
      (node (ref "R30") (pin "1") (pinfunction "1_1") (pintype "passive"))
    )
    (net (code "56") (name "Net-(Q4-B)") (class "Default")
      (node (ref "Q4") (pin "1") (pinfunction "B_1") (pintype "passive"))
      (node (ref "R28") (pin "1") (pinfunction "1_1") (pintype "passive"))
      (node (ref "R31") (pin "1") (pinfunction "1_1") (pintype "passive"))
    )
    (net (code "57") (name "Net-(Q5-B)") (class "Default")
      (node (ref "Q5") (pin "1") (pinfunction "B_1") (pintype "passive"))
      (node (ref "R29") (pin "1") (pinfunction "1_1") (pintype "passive"))
      (node (ref "R35") (pin "1") (pinfunction "1_1") (pintype "passive"))
    )
    (net (code "58") (name "Net-(Q6-B)") (class "Default")
      (node (ref "Q6") (pin "1") (pinfunction "B_1") (pintype "passive"))
      (node (ref "R32") (pin "1") (pinfunction "1_1") (pintype "passive"))
      (node (ref "R36") (pin "1") (pinfunction "1_1") (pintype "passive"))
    )
    (net (code "59") (name "Net-(Q7-B)") (class "Default")
      (node (ref "Q7") (pin "1") (pinfunction "B_1") (pintype "passive"))
      (node (ref "R33") (pin "1") (pinfunction "1_1") (pintype "passive"))
      (node (ref "R37") (pin "1") (pinfunction "1_1") (pintype "passive"))
    )
    (net (code "60") (name "Net-(Q8-B)") (class "Default")
      (node (ref "Q8") (pin "1") (pinfunction "B_1") (pintype "passive"))
      (node (ref "R34") (pin "1") (pinfunction "1_1") (pintype "passive"))
      (node (ref "R38") (pin "1") (pinfunction "1_1") (pintype "passive"))
    )
    (net (code "61") (name "Net-(Q9-G1)") (class "Default")
      (node (ref "C20") (pin "2") (pinfunction "2_2") (pintype "passive"))
      (node (ref "Q9") (pin "1") (pinfunction "G1_1") (pintype "passive"))
      (node (ref "R39") (pin "1") (pinfunction "1_1") (pintype "passive"))
      (node (ref "R40") (pin "1") (pinfunction "1_1") (pintype "passive"))
    )
    (net (code "62") (name "Net-(Q9-G2)") (class "Default")
      (node (ref "C21") (pin "2") (pinfunction "2_2") (pintype "passive"))
      (node (ref "Q9") (pin "8") (pinfunction "G2_8") (pintype "passive"))
      (node (ref "R41") (pin "1") (pinfunction "1_1") (pintype "passive"))
      (node (ref "R42") (pin "1") (pinfunction "1_1") (pintype "passive"))
    )
    (net (code "63") (name "Net-(R5-Pad2)") (class "Default")
      (node (ref "R5") (pin "2") (pinfunction "2_2") (pintype "passive"))
      (node (ref "R9") (pin "1") (pinfunction "1_1") (pintype "passive"))
    )
    (net (code "64") (name "Net-(U1-FB)") (class "Default")
      (node (ref "C7") (pin "1") (pinfunction "1_1") (pintype "passive"))
      (node (ref "R2") (pin "2") (pinfunction "2_2") (pintype "passive"))
      (node (ref "R5") (pin "1") (pinfunction "1_1") (pintype "passive"))
      (node (ref "U1") (pin "3") (pinfunction "FB_3") (pintype "passive"))
    )
    (net (code "65") (name "Net-(U1-GVDD)") (class "Default")
      (node (ref "C1") (pin "2") (pinfunction "2_2") (pintype "passive"))
      (node (ref "U1") (pin "1") (pinfunction "GVDD_1") (pintype "passive"))
    )
    (net (code "66") (name "Net-(U1-LX)") (class "Default")
      (node (ref "L1") (pin "1") (pinfunction "1_1") (pintype "passive"))
      (node (ref "U1") (pin "6") (pinfunction "LX_6") (pintype "passive"))
    )
    (net (code "67") (name "Net-(U2-ICHG)") (class "Default")
      (node (ref "R3") (pin "1") (pinfunction "1_1") (pintype "passive"))
      (node (ref "U2") (pin "6") (pinfunction "ICHG_6") (pintype "passive"))
    )
    (net (code "68") (name "Net-(U4-AVDD)") (class "Default")
      (node (ref "C29") (pin "2") (pinfunction "2_2") (pintype "passive"))
      (node (ref "U4") (pin "3") (pinfunction "AVDD_3") (pintype "passive"))
    )
    (net (code "69") (name "Net-(U4-P0.2{slash}RSTN)") (class "Default")
      (node (ref "C28") (pin "1") (pinfunction "1_1") (pintype "passive"))
      (node (ref "U4") (pin "2") (pinfunction "P0.2/RSTN_2") (pintype "passive"))
    )
    (net (code "70") (name "PGND") (class "Default")
      (node (ref "C13") (pin "1") (pinfunction "1_1") (pintype "passive"))
      (node (ref "C18") (pin "1") (pinfunction "1_1") (pintype "passive"))
      (node (ref "C21") (pin "1") (pinfunction "1_1") (pintype "passive"))
      (node (ref "FU1") (pin "2") (pinfunction "2_2") (pintype "passive"))
      (node (ref "Q1") (pin "5") (pinfunction "S2_5") (pintype "passive"))
      (node (ref "Q1") (pin "6") (pinfunction "S2_6") (pintype "passive"))
      (node (ref "Q1") (pin "7") (pinfunction "S2_7") (pintype "passive"))
      (node (ref "Q2") (pin "5") (pinfunction "S2_5") (pintype "passive"))
      (node (ref "Q2") (pin "6") (pinfunction "S2_6") (pintype "passive"))
      (node (ref "Q2") (pin "7") (pinfunction "S2_7") (pintype "passive"))
      (node (ref "Q9") (pin "5") (pinfunction "S2_5") (pintype "passive"))
      (node (ref "Q9") (pin "6") (pinfunction "S2_6") (pintype "passive"))
      (node (ref "Q9") (pin "7") (pinfunction "S2_7") (pintype "passive"))
      (node (ref "R12") (pin "2") (pinfunction "2_2") (pintype "passive"))
      (node (ref "R26") (pin "2") (pinfunction "2_2") (pintype "passive"))
      (node (ref "R42") (pin "2") (pinfunction "2_2") (pintype "passive"))
      (node (ref "R45") (pin "1") (pinfunction "1_1") (pintype "passive"))
      (node (ref "R48") (pin "1") (pinfunction "1_1") (pintype "passive"))
      (node (ref "R49") (pin "1") (pinfunction "1_1") (pintype "passive"))
    )
    (net (code "71") (name "VBAT_8V4") (class "Default")
      (node (ref "C14") (pin "2") (pinfunction "2_2") (pintype "passive"))
      (node (ref "C15") (pin "2") (pinfunction "2_2") (pintype "passive"))
      (node (ref "C6") (pin "2") (pinfunction "2_2") (pintype "passive"))
      (node (ref "DS1") (pin "1") (pinfunction "A_1") (pintype "passive"))
      (node (ref "P6") (pin "2") (pinfunction "2_2") (pintype "passive"))
      (node (ref "Q1") (pin "2") (pinfunction "D1_2") (pintype "passive"))
      (node (ref "Q1") (pin "3") (pinfunction "D1_3") (pintype "passive"))
      (node (ref "Q1") (pin "4") (pinfunction "D1_4") (pintype "passive"))
      (node (ref "Q1") (pin "9") (pinfunction "D1_9") (pintype "passive"))
      (node (ref "Q2") (pin "2") (pinfunction "D1_2") (pintype "passive"))
      (node (ref "Q2") (pin "3") (pinfunction "D1_3") (pintype "passive"))
      (node (ref "Q2") (pin "4") (pinfunction "D1_4") (pintype "passive"))
      (node (ref "Q2") (pin "9") (pinfunction "D1_9") (pintype "passive"))
      (node (ref "Q9") (pin "2") (pinfunction "D1_2") (pintype "passive"))
      (node (ref "Q9") (pin "3") (pinfunction "D1_3") (pintype "passive"))
      (node (ref "Q9") (pin "4") (pinfunction "D1_4") (pintype "passive"))
      (node (ref "Q9") (pin "9") (pinfunction "D1_9") (pintype "passive"))
      (node (ref "R13") (pin "1") (pinfunction "1_1") (pintype "passive"))
      (node (ref "R44") (pin "1") (pinfunction "1_1") (pintype "passive"))
      (node (ref "R8") (pin "2") (pinfunction "2_2") (pintype "passive"))
      (node (ref "U1") (pin "5") (pinfunction "VIN_5") (pintype "passive"))
      (node (ref "U2") (pin "5") (pinfunction "BAT_5") (pintype "passive"))
      (node (ref "U4") (pin "27") (pinfunction "VCC_27") (pintype "passive"))
    )
    (net (code "72") (name "unconnected-(U2-NTC-Pad7)") (class "Default")
      (node (ref "U2") (pin "7") (pinfunction "NTC_7") (pintype "passive"))
    )
    (net (code "73") (name "unconnected-(U4-CMP1_OUT{slash}HALL_IN1{slash}UART1_TXD{slash}TIM1_CH1{slash}CMP1_IP2{slash}P2.5{slash}CMP2_OUT{slash}HALL_IN2{slash}P2.6-Pad39)") (class "Default")
      (node (ref "U4") (pin "39") (pinfunction "CMP1_OUT/HALL_IN1/UART1_TXD/TIM1_CH1/CMP1_IP2/P2.5/CMP2_OUT/HALL_IN2/P2.6_39") (pintype "passive"))
    )
    (net (code "74") (name "unconnected-(U4-GND-Pad17)") (class "Default")
      (node (ref "U4") (pin "17") (pinfunction "GND_17") (pintype "passive+no_connect"))
    )
    (net (code "75") (name "unconnected-(U4-MCPWM_CH4N{slash}OPA2_IN{slash}P3.11-Pad32)") (class "Default")
      (node (ref "U4") (pin "32") (pinfunction "MCPWM_CH4N/OPA2_IN/P3.11_32") (pintype "passive"))
    )
    (net (code "76") (name "unconnected-(U4-MCPWM_CH4P{slash}OPA2_IP{slash}P3.10-Pad31)") (class "Default")
      (node (ref "U4") (pin "31") (pinfunction "MCPWM_CH4P/OPA2_IP/P3.10_31") (pintype "passive"))
    )
    (net (code "77") (name "unconnected-(U4-MCPWM_CH5N{slash}SPI_DO{slash}SDA{slash}P2.10-Pad34)") (class "Default")
      (node (ref "U4") (pin "34") (pinfunction "MCPWM_CH5N/SPI_DO/SDA/P2.10_34") (pintype "passive+no_connect"))
    )
    (net (code "78") (name "unconnected-(U4-OPA3_IN{slash}P3.14-Pad35)") (class "Default")
      (node (ref "U4") (pin "35") (pinfunction "OPA3_IN/P3.14_35") (pintype "passive+no_connect"))
    )
    (net (code "79") (name "unconnected-(U4-P0.15{slash}CMP2_OUT{slash}MCPWM_CH0P{slash}UART0_RXD{slash}SPI_DO{slash}SDA{slash}TIM0_CH0{slash}CMP0_IN-Pad12)") (class "Default")
      (node (ref "U4") (pin "12") (pinfunction "P0.15/CMP2_OUT/MCPWM_CH0P/UART0_RXD/SPI_DO/SDA/TIM0_CH0/CMP0_IN_12") (pintype "passive+no_connect"))
    )
    (net (code "80") (name "unconnected-(U4-P1.0{slash}MCPWM_CH0N{slash}UART0_TXD{slash}SPI_DI-Pad13)") (class "Default")
      (node (ref "U4") (pin "13") (pinfunction "P1.0/MCPWM_CH0N/UART0_TXD/SPI_DI_13") (pintype "passive+no_connect"))
    )
  )
)
